# moduloAcionamento2.net
KiCad netlist of a schematic drawn in EAGLE
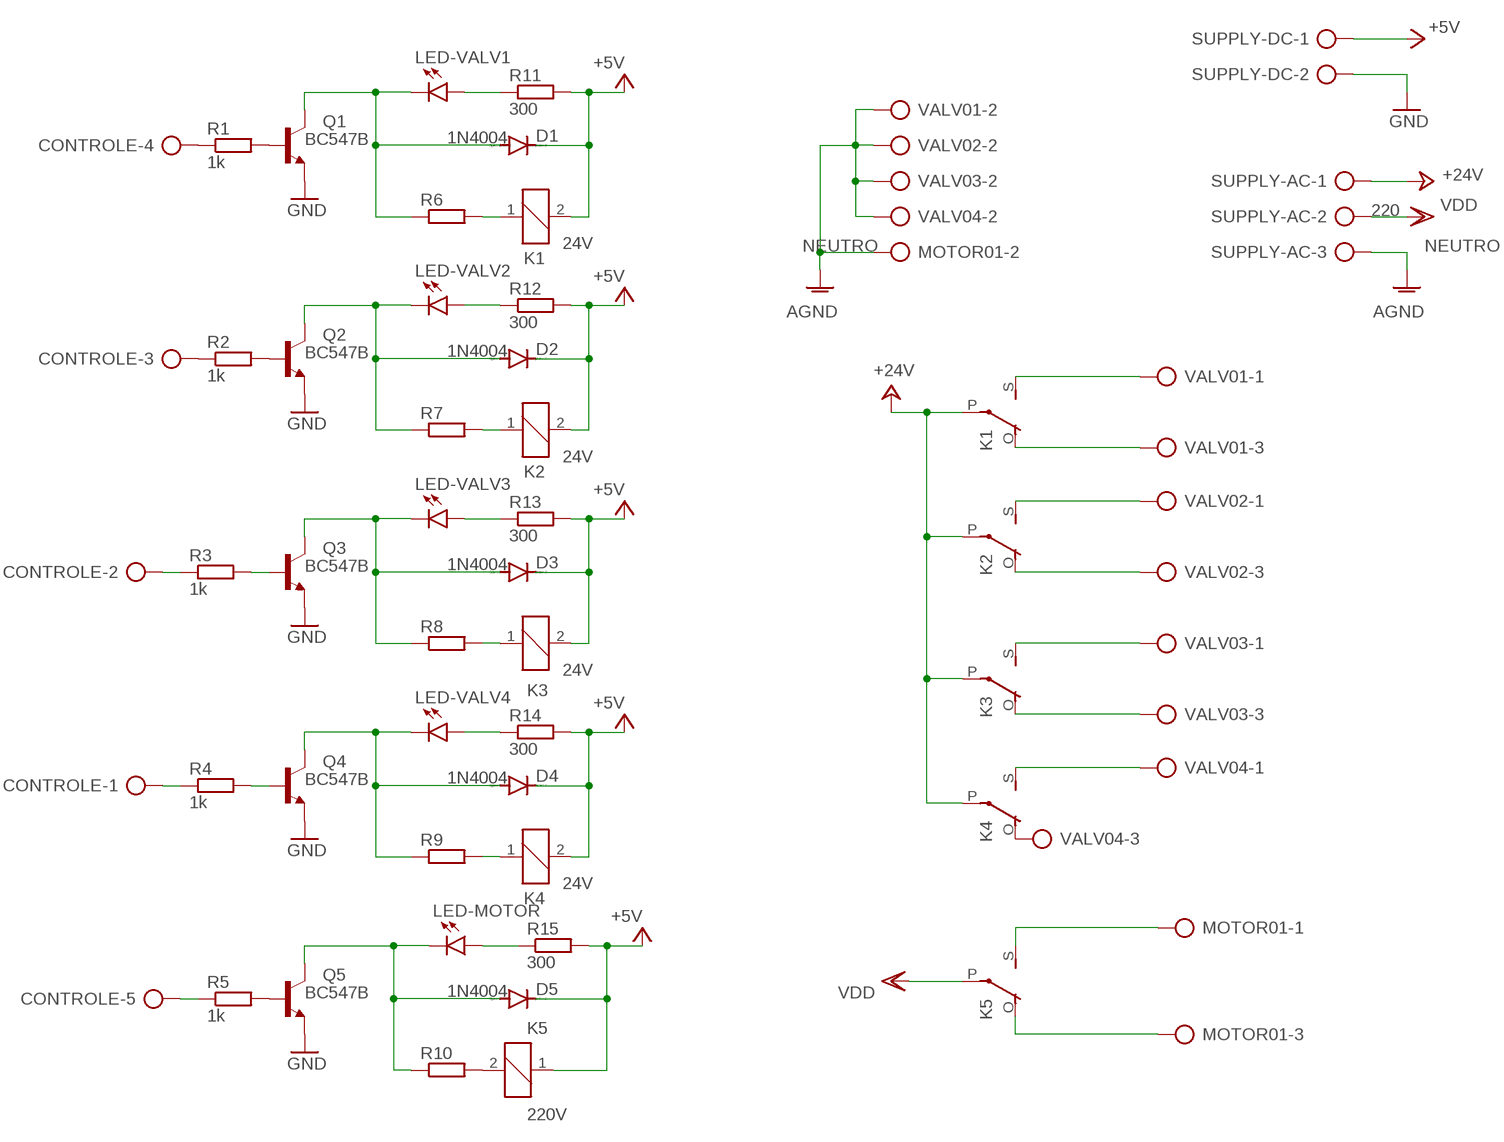
[diagram p0: schematic, sheet 1]

(export (version "E")
  (design (tool "Eeschema 10.0.6"))
  (components
    (comp (ref "CONTROLE")
      (value "AK500/5")
      (footprint "eagle-import:AK500_5")
      (libsource (lib "eagle-import") (part "AK500/5"))
    )
    (comp (ref "D1")
      (value "1N4004")
      (footprint "eagle-import:DO41-10")
      (libsource (lib "eagle-import") (part "1N4004"))
    )
    (comp (ref "D2")
      (value "1N4004")
      (footprint "eagle-import:DO41-10")
      (libsource (lib "eagle-import") (part "1N4004"))
    )
    (comp (ref "D3")
      (value "1N4004")
      (footprint "eagle-import:DO41-10")
      (libsource (lib "eagle-import") (part "1N4004"))
    )
    (comp (ref "D4")
      (value "1N4004")
      (footprint "eagle-import:DO41-10")
      (libsource (lib "eagle-import") (part "1N4004"))
    )
    (comp (ref "D5")
      (value "1N4004")
      (footprint "eagle-import:DO41-10")
      (libsource (lib "eagle-import") (part "1N4004"))
    )
    (comp (ref "K1")
      (value "24V")
      (footprint "eagle-import:G5LE")
      (libsource (lib "eagle-import") (part "G5L"))
    )
    (comp (ref "K2")
      (value "24V")
      (footprint "eagle-import:G5LE")
      (libsource (lib "eagle-import") (part "G5L"))
    )
    (comp (ref "K3")
      (value "24V")
      (footprint "eagle-import:G5LE")
      (libsource (lib "eagle-import") (part "G5L"))
    )
    (comp (ref "K4")
      (value "24V")
      (footprint "eagle-import:G5LE")
      (libsource (lib "eagle-import") (part "G5L"))
    )
    (comp (ref "K5")
      (value "220V")
      (footprint "eagle-import:G5LE")
      (libsource (lib "eagle-import") (part "G5L"))
    )
    (comp (ref "LED-MOTOR")
      (value "LED5MM")
      (footprint "eagle-import:LED5MM")
      (libsource (lib "eagle-import") (part "LED5MM"))
    )
    (comp (ref "LED-VALV1")
      (value "LED5MM")
      (footprint "eagle-import:LED5MM")
      (libsource (lib "eagle-import") (part "LED5MM"))
    )
    (comp (ref "LED-VALV2")
      (value "LED5MM")
      (footprint "eagle-import:LED5MM")
      (libsource (lib "eagle-import") (part "LED5MM"))
    )
    (comp (ref "LED-VALV3")
      (value "LED5MM")
      (footprint "eagle-import:LED5MM")
      (libsource (lib "eagle-import") (part "LED5MM"))
    )
    (comp (ref "LED-VALV4")
      (value "LED5MM")
      (footprint "eagle-import:LED5MM")
      (libsource (lib "eagle-import") (part "LED5MM"))
    )
    (comp (ref "MOTOR01")
      (value "AK500/3")
      (footprint "eagle-import:AK500_3")
      (libsource (lib "eagle-import") (part "AK500/3"))
    )
    (comp (ref "Q1")
      (value "BC547B")
      (footprint "eagle-import:TO92")
      (libsource (lib "eagle-import") (part "BC547B"))
    )
    (comp (ref "Q2")
      (value "BC547B")
      (footprint "eagle-import:TO92")
      (libsource (lib "eagle-import") (part "BC547B"))
    )
    (comp (ref "Q3")
      (value "BC547B")
      (footprint "eagle-import:TO92")
      (libsource (lib "eagle-import") (part "BC547B"))
    )
    (comp (ref "Q4")
      (value "BC547B")
      (footprint "eagle-import:TO92")
      (libsource (lib "eagle-import") (part "BC547B"))
    )
    (comp (ref "Q5")
      (value "BC547B")
      (footprint "eagle-import:TO92")
      (libsource (lib "eagle-import") (part "BC547B"))
    )
    (comp (ref "R1")
      (value "1k")
      (footprint "eagle-import:0204_7")
      (libsource (lib "eagle-import") (part "R-EU_0204/7"))
    )
    (comp (ref "R2")
      (value "1k")
      (footprint "eagle-import:0204_7")
      (libsource (lib "eagle-import") (part "R-EU_0204/7"))
    )
    (comp (ref "R3")
      (value "1k")
      (footprint "eagle-import:0204_7")
      (libsource (lib "eagle-import") (part "R-EU_0204/7"))
    )
    (comp (ref "R4")
      (value "1k")
      (footprint "eagle-import:0204_7")
      (libsource (lib "eagle-import") (part "R-EU_0204/7"))
    )
    (comp (ref "R5")
      (value "1k")
      (footprint "eagle-import:0204_7")
      (libsource (lib "eagle-import") (part "R-EU_0204/7"))
    )
    (comp (ref "R6")
      (value "R-EU_0204/7")
      (footprint "eagle-import:0204_7")
      (libsource (lib "eagle-import") (part "R-EU_0204/7"))
    )
    (comp (ref "R7")
      (value "R-EU_0204/7")
      (footprint "eagle-import:0204_7")
      (libsource (lib "eagle-import") (part "R-EU_0204/7"))
    )
    (comp (ref "R8")
      (value "R-EU_0204/7")
      (footprint "eagle-import:0204_7")
      (libsource (lib "eagle-import") (part "R-EU_0204/7"))
    )
    (comp (ref "R9")
      (value "R-EU_0204/7")
      (footprint "eagle-import:0204_7")
      (libsource (lib "eagle-import") (part "R-EU_0204/7"))
    )
    (comp (ref "R10")
      (value "R-EU_0204/7")
      (footprint "eagle-import:0204_7")
      (libsource (lib "eagle-import") (part "R-EU_0204/7"))
    )
    (comp (ref "R11")
      (value "300")
      (footprint "eagle-import:0204_7")
      (libsource (lib "eagle-import") (part "R-EU_0204/7"))
    )
    (comp (ref "R12")
      (value "300")
      (footprint "eagle-import:0204_7")
      (libsource (lib "eagle-import") (part "R-EU_0204/7"))
    )
    (comp (ref "R13")
      (value "300")
      (footprint "eagle-import:0204_7")
      (libsource (lib "eagle-import") (part "R-EU_0204/7"))
    )
    (comp (ref "R14")
      (value "300")
      (footprint "eagle-import:0204_7")
      (libsource (lib "eagle-import") (part "R-EU_0204/7"))
    )
    (comp (ref "R15")
      (value "300")
      (footprint "eagle-import:0204_7")
      (libsource (lib "eagle-import") (part "R-EU_0204/7"))
    )
    (comp (ref "SUPPLY-AC")
      (value "AK500/3")
      (footprint "eagle-import:AK500_3")
      (libsource (lib "eagle-import") (part "AK500/3"))
    )
    (comp (ref "SUPPLY-DC")
      (value "AK500/2")
      (footprint "eagle-import:AK500_2")
      (libsource (lib "eagle-import") (part "AK500/2"))
    )
    (comp (ref "VALV01")
      (value "AK500/3")
      (footprint "eagle-import:AK500_3")
      (libsource (lib "eagle-import") (part "AK500/3"))
    )
    (comp (ref "VALV02")
      (value "AK500/3")
      (footprint "eagle-import:AK500_3")
      (libsource (lib "eagle-import") (part "AK500/3"))
    )
    (comp (ref "VALV03")
      (value "AK500/3")
      (footprint "eagle-import:AK500_3")
      (libsource (lib "eagle-import") (part "AK500/3"))
    )
    (comp (ref "VALV04")
      (value "AK500/3")
      (footprint "eagle-import:AK500_3")
      (libsource (lib "eagle-import") (part "AK500/3"))
    )
  )
  (nets
    (net (code "1") (name "+5V") (class "Default")
      (node (ref "D1") (pin "C") (pinfunction "C_C") (pintype "passive"))
      (node (ref "D2") (pin "C") (pinfunction "C_C") (pintype "passive"))
      (node (ref "D3") (pin "C") (pinfunction "C_C") (pintype "passive"))
      (node (ref "D4") (pin "C") (pinfunction "C_C") (pintype "passive"))
      (node (ref "D5") (pin "C") (pinfunction "C_C") (pintype "passive"))
      (node (ref "K1") (pin "2") (pinfunction "2_2") (pintype "passive"))
      (node (ref "K2") (pin "2") (pinfunction "2_2") (pintype "passive"))
      (node (ref "K3") (pin "2") (pinfunction "2_2") (pintype "passive"))
      (node (ref "K4") (pin "2") (pinfunction "2_2") (pintype "passive"))
      (node (ref "K5") (pin "1") (pinfunction "1_1") (pintype "passive"))
      (node (ref "R11") (pin "2") (pinfunction "2_2") (pintype "passive"))
      (node (ref "R12") (pin "2") (pinfunction "2_2") (pintype "passive"))
      (node (ref "R13") (pin "2") (pinfunction "2_2") (pintype "passive"))
      (node (ref "R14") (pin "2") (pinfunction "2_2") (pintype "passive"))
      (node (ref "R15") (pin "2") (pinfunction "2_2") (pintype "passive"))
      (node (ref "SUPPLY-DC") (pin "1") (pinfunction "KL_1") (pintype "passive"))
    )
    (net (code "2") (name "+24V") (class "Default")
      (node (ref "K1") (pin "P") (pinfunction "P_P") (pintype "passive"))
      (node (ref "K2") (pin "P") (pinfunction "P_P") (pintype "passive"))
      (node (ref "K3") (pin "P") (pinfunction "P_P") (pintype "passive"))
      (node (ref "K4") (pin "P") (pinfunction "P_P") (pintype "passive"))
      (node (ref "SUPPLY-AC") (pin "1") (pinfunction "KL_1") (pintype "passive"))
    )
    (net (code "3") (name "AGND") (class "Default")
      (node (ref "MOTOR01") (pin "2") (pinfunction "KL_2") (pintype "passive"))
      (node (ref "SUPPLY-AC") (pin "3") (pinfunction "KL_3") (pintype "passive"))
      (node (ref "VALV01") (pin "2") (pinfunction "KL_2") (pintype "passive"))
      (node (ref "VALV02") (pin "2") (pinfunction "KL_2") (pintype "passive"))
      (node (ref "VALV03") (pin "2") (pinfunction "KL_2") (pintype "passive"))
      (node (ref "VALV04") (pin "2") (pinfunction "KL_2") (pintype "passive"))
    )
    (net (code "4") (name "GND") (class "Default")
      (node (ref "Q1") (pin "1") (pinfunction "E_1") (pintype "passive"))
      (node (ref "Q2") (pin "1") (pinfunction "E_1") (pintype "passive"))
      (node (ref "Q3") (pin "1") (pinfunction "E_1") (pintype "passive"))
      (node (ref "Q4") (pin "1") (pinfunction "E_1") (pintype "passive"))
      (node (ref "Q5") (pin "1") (pinfunction "E_1") (pintype "passive"))
      (node (ref "SUPPLY-DC") (pin "2") (pinfunction "KL_2") (pintype "passive"))
    )
    (net (code "5") (name "Net-(CONTROLEA-KL)") (class "Default")
      (node (ref "CONTROLE") (pin "1") (pinfunction "KL_1") (pintype "passive"))
      (node (ref "R4") (pin "1") (pinfunction "1_1") (pintype "passive"))
    )
    (net (code "6") (name "Net-(CONTROLEB-KL)") (class "Default")
      (node (ref "CONTROLE") (pin "2") (pinfunction "KL_2") (pintype "passive"))
      (node (ref "R3") (pin "1") (pinfunction "1_1") (pintype "passive"))
    )
    (net (code "7") (name "Net-(CONTROLEC-KL)") (class "Default")
      (node (ref "CONTROLE") (pin "3") (pinfunction "KL_3") (pintype "passive"))
      (node (ref "R2") (pin "1") (pinfunction "1_1") (pintype "passive"))
    )
    (net (code "8") (name "Net-(CONTROLED-KL)") (class "Default")
      (node (ref "CONTROLE") (pin "4") (pinfunction "KL_4") (pintype "passive"))
      (node (ref "R1") (pin "1") (pinfunction "1_1") (pintype "passive"))
    )
    (net (code "9") (name "Net-(CONTROLEE-KL)") (class "Default")
      (node (ref "CONTROLE") (pin "5") (pinfunction "KL_5") (pintype "passive"))
      (node (ref "R5") (pin "1") (pinfunction "1_1") (pintype "passive"))
    )
    (net (code "10") (name "Net-(K1-Pad1)") (class "Default")
      (node (ref "K1") (pin "1") (pinfunction "1_1") (pintype "passive"))
      (node (ref "R6") (pin "2") (pinfunction "2_2") (pintype "passive"))
    )
    (net (code "11") (name "Net-(K2-Pad1)") (class "Default")
      (node (ref "K2") (pin "1") (pinfunction "1_1") (pintype "passive"))
      (node (ref "R7") (pin "2") (pinfunction "2_2") (pintype "passive"))
    )
    (net (code "12") (name "Net-(K3-Pad1)") (class "Default")
      (node (ref "K3") (pin "1") (pinfunction "1_1") (pintype "passive"))
      (node (ref "R8") (pin "2") (pinfunction "2_2") (pintype "passive"))
    )
    (net (code "13") (name "Net-(K4-Pad1)") (class "Default")
      (node (ref "K4") (pin "1") (pinfunction "1_1") (pintype "passive"))
      (node (ref "R9") (pin "2") (pinfunction "2_2") (pintype "passive"))
    )
    (net (code "14") (name "Net-(K5-Pad2)") (class "Default")
      (node (ref "K5") (pin "2") (pinfunction "2_2") (pintype "passive"))
      (node (ref "R10") (pin "2") (pinfunction "2_2") (pintype "passive"))
    )
    (net (code "15") (name "Net-(LED-MOTOR-C)") (class "Default")
      (node (ref "D5") (pin "A") (pinfunction "A_A") (pintype "passive"))
      (node (ref "LED-MOTOR") (pin "K") (pinfunction "C_K") (pintype "passive"))
      (node (ref "Q5") (pin "3") (pinfunction "C_3") (pintype "passive"))
      (node (ref "R10") (pin "1") (pinfunction "1_1") (pintype "passive"))
    )
    (net (code "16") (name "Net-(LED-MOTOR-PadA)") (class "Default")
      (node (ref "LED-MOTOR") (pin "A") (pinfunction "A_A") (pintype "passive"))
      (node (ref "R15") (pin "1") (pinfunction "1_1") (pintype "passive"))
    )
    (net (code "17") (name "Net-(LED-VALV1-C)") (class "Default")
      (node (ref "D1") (pin "A") (pinfunction "A_A") (pintype "passive"))
      (node (ref "LED-VALV1") (pin "K") (pinfunction "C_K") (pintype "passive"))
      (node (ref "Q1") (pin "3") (pinfunction "C_3") (pintype "passive"))
      (node (ref "R6") (pin "1") (pinfunction "1_1") (pintype "passive"))
    )
    (net (code "18") (name "Net-(LED-VALV1-PadA)") (class "Default")
      (node (ref "LED-VALV1") (pin "A") (pinfunction "A_A") (pintype "passive"))
      (node (ref "R11") (pin "1") (pinfunction "1_1") (pintype "passive"))
    )
    (net (code "19") (name "Net-(LED-VALV2-C)") (class "Default")
      (node (ref "D2") (pin "A") (pinfunction "A_A") (pintype "passive"))
      (node (ref "LED-VALV2") (pin "K") (pinfunction "C_K") (pintype "passive"))
      (node (ref "Q2") (pin "3") (pinfunction "C_3") (pintype "passive"))
      (node (ref "R7") (pin "1") (pinfunction "1_1") (pintype "passive"))
    )
    (net (code "20") (name "Net-(LED-VALV2-PadA)") (class "Default")
      (node (ref "LED-VALV2") (pin "A") (pinfunction "A_A") (pintype "passive"))
      (node (ref "R12") (pin "1") (pinfunction "1_1") (pintype "passive"))
    )
    (net (code "21") (name "Net-(LED-VALV3-C)") (class "Default")
      (node (ref "D3") (pin "A") (pinfunction "A_A") (pintype "passive"))
      (node (ref "LED-VALV3") (pin "K") (pinfunction "C_K") (pintype "passive"))
      (node (ref "Q3") (pin "3") (pinfunction "C_3") (pintype "passive"))
      (node (ref "R8") (pin "1") (pinfunction "1_1") (pintype "passive"))
    )
    (net (code "22") (name "Net-(LED-VALV3-PadA)") (class "Default")
      (node (ref "LED-VALV3") (pin "A") (pinfunction "A_A") (pintype "passive"))
      (node (ref "R13") (pin "1") (pinfunction "1_1") (pintype "passive"))
    )
    (net (code "23") (name "Net-(LED-VALV4-C)") (class "Default")
      (node (ref "D4") (pin "A") (pinfunction "A_A") (pintype "passive"))
      (node (ref "LED-VALV4") (pin "K") (pinfunction "C_K") (pintype "passive"))
      (node (ref "Q4") (pin "3") (pinfunction "C_3") (pintype "passive"))
      (node (ref "R9") (pin "1") (pinfunction "1_1") (pintype "passive"))
    )
    (net (code "24") (name "Net-(LED-VALV4-PadA)") (class "Default")
      (node (ref "LED-VALV4") (pin "A") (pinfunction "A_A") (pintype "passive"))
      (node (ref "R14") (pin "1") (pinfunction "1_1") (pintype "passive"))
    )
    (net (code "25") (name "Net-(MOTOR01A-KL)") (class "Default")
      (node (ref "K5") (pin "S") (pinfunction "S_S") (pintype "passive"))
      (node (ref "MOTOR01") (pin "1") (pinfunction "KL_1") (pintype "passive"))
    )
    (net (code "26") (name "Net-(MOTOR01C-KL)") (class "Default")
      (node (ref "K5") (pin "O") (pinfunction "O_O") (pintype "passive"))
      (node (ref "MOTOR01") (pin "3") (pinfunction "KL_3") (pintype "passive"))
    )
    (net (code "27") (name "Net-(Q1-B)") (class "Default")
      (node (ref "Q1") (pin "2") (pinfunction "B_2") (pintype "passive"))
      (node (ref "R1") (pin "2") (pinfunction "2_2") (pintype "passive"))
    )
    (net (code "28") (name "Net-(Q2-B)") (class "Default")
      (node (ref "Q2") (pin "2") (pinfunction "B_2") (pintype "passive"))
      (node (ref "R2") (pin "2") (pinfunction "2_2") (pintype "passive"))
    )
    (net (code "29") (name "Net-(Q3-B)") (class "Default")
      (node (ref "Q3") (pin "2") (pinfunction "B_2") (pintype "passive"))
      (node (ref "R3") (pin "2") (pinfunction "2_2") (pintype "passive"))
    )
    (net (code "30") (name "Net-(Q4-B)") (class "Default")
      (node (ref "Q4") (pin "2") (pinfunction "B_2") (pintype "passive"))
      (node (ref "R4") (pin "2") (pinfunction "2_2") (pintype "passive"))
    )
    (net (code "31") (name "Net-(Q5-B)") (class "Default")
      (node (ref "Q5") (pin "2") (pinfunction "B_2") (pintype "passive"))
      (node (ref "R5") (pin "2") (pinfunction "2_2") (pintype "passive"))
    )
    (net (code "32") (name "Net-(VALV01A-KL)") (class "Default")
      (node (ref "K1") (pin "S") (pinfunction "S_S") (pintype "passive"))
      (node (ref "VALV01") (pin "1") (pinfunction "KL_1") (pintype "passive"))
    )
    (net (code "33") (name "Net-(VALV01C-KL)") (class "Default")
      (node (ref "K1") (pin "O") (pinfunction "O_O") (pintype "passive"))
      (node (ref "VALV01") (pin "3") (pinfunction "KL_3") (pintype "passive"))
    )
    (net (code "34") (name "Net-(VALV02A-KL)") (class "Default")
      (node (ref "K2") (pin "S") (pinfunction "S_S") (pintype "passive"))
      (node (ref "VALV02") (pin "1") (pinfunction "KL_1") (pintype "passive"))
    )
    (net (code "35") (name "Net-(VALV02C-KL)") (class "Default")
      (node (ref "K2") (pin "O") (pinfunction "O_O") (pintype "passive"))
      (node (ref "VALV02") (pin "3") (pinfunction "KL_3") (pintype "passive"))
    )
    (net (code "36") (name "Net-(VALV03A-KL)") (class "Default")
      (node (ref "K3") (pin "S") (pinfunction "S_S") (pintype "passive"))
      (node (ref "VALV03") (pin "1") (pinfunction "KL_1") (pintype "passive"))
    )
    (net (code "37") (name "Net-(VALV03C-KL)") (class "Default")
      (node (ref "K3") (pin "O") (pinfunction "O_O") (pintype "passive"))
      (node (ref "VALV03") (pin "3") (pinfunction "KL_3") (pintype "passive"))
    )
    (net (code "38") (name "Net-(VALV04A-KL)") (class "Default")
      (node (ref "K4") (pin "S") (pinfunction "S_S") (pintype "passive"))
      (node (ref "VALV04") (pin "1") (pinfunction "KL_1") (pintype "passive"))
    )
    (net (code "39") (name "Net-(VALV04C-KL)") (class "Default")
      (node (ref "K4") (pin "O") (pinfunction "O_O") (pintype "passive"))
      (node (ref "VALV04") (pin "3") (pinfunction "KL_3") (pintype "passive"))
    )
    (net (code "40") (name "VDD") (class "Default")
      (node (ref "K5") (pin "P") (pinfunction "P_P") (pintype "passive"))
      (node (ref "SUPPLY-AC") (pin "2") (pinfunction "KL_2") (pintype "passive"))
    )
  )
)
